# IRis_-_Slave_Schematic.net
KiCad netlist of a schematic drawn in EAGLE
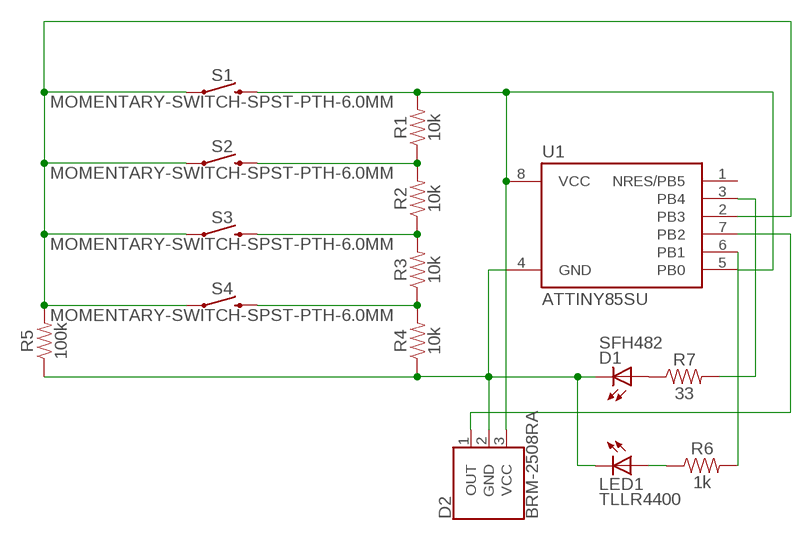
[diagram p0: schematic, sheet 1]

(export (version "E")
  (design (tool "Eeschema 10.0.6"))
  (components
    (comp (ref "D1")
      (value "SFH482")
      (footprint "eagle-import:SFH482")
      (libsource (lib "eagle-import") (part "SFH482"))
    )
    (comp (ref "D2")
      (value "BRM-2508RA")
      (footprint "eagle-import:BRM-2508")
      (libsource (lib "eagle-import") (part "BRM-2508RA"))
    )
    (comp (ref "LED1")
      (value "TLLR4400")
      (footprint "eagle-import:LED3MM")
      (fields (field (name "MF") "VISHAY SEMICONDUCTOR"))
      (libsource (lib "eagle-import") (part "TLLR4400"))
    )
    (comp (ref "R1")
      (value "10k")
      (footprint "eagle-import:AXIAL-0.3")
      (libsource (lib "eagle-import") (part "10KOHM-HORIZ-1/4W-5%"))
    )
    (comp (ref "R2")
      (value "10k")
      (footprint "eagle-import:AXIAL-0.3")
      (libsource (lib "eagle-import") (part "10KOHM-HORIZ-1/4W-5%"))
    )
    (comp (ref "R3")
      (value "10k")
      (footprint "eagle-import:AXIAL-0.3")
      (libsource (lib "eagle-import") (part "10KOHM-HORIZ-1/4W-5%"))
    )
    (comp (ref "R4")
      (value "10k")
      (footprint "eagle-import:AXIAL-0.3")
      (libsource (lib "eagle-import") (part "10KOHM-HORIZ-1/4W-5%"))
    )
    (comp (ref "R5")
      (value "100k")
      (footprint "eagle-import:AXIAL-0.3")
      (libsource (lib "eagle-import") (part "100KOHM-HORIZ-1/4W-5%"))
    )
    (comp (ref "R6")
      (value "1k")
      (footprint "eagle-import:AXIAL-0.3")
      (libsource (lib "eagle-import") (part "1KOHM-HORIZ-1/4W-5%"))
    )
    (comp (ref "R7")
      (value "33")
      (footprint "eagle-import:0603")
      (libsource (lib "eagle-import") (part "33OHM-0603-1/10W-1%"))
    )
    (comp (ref "S1")
      (value "MOMENTARY-SWITCH-SPST-PTH-6.0MM")
      (footprint "eagle-import:TACTILE_SWITCH_PTH_6.0MM")
      (libsource (lib "eagle-import") (part "MOMENTARY-SWITCH-SPST-PTH-6.0MM"))
    )
    (comp (ref "S2")
      (value "MOMENTARY-SWITCH-SPST-PTH-6.0MM")
      (footprint "eagle-import:TACTILE_SWITCH_PTH_6.0MM")
      (libsource (lib "eagle-import") (part "MOMENTARY-SWITCH-SPST-PTH-6.0MM"))
    )
    (comp (ref "S3")
      (value "MOMENTARY-SWITCH-SPST-PTH-6.0MM")
      (footprint "eagle-import:TACTILE_SWITCH_PTH_6.0MM")
      (libsource (lib "eagle-import") (part "MOMENTARY-SWITCH-SPST-PTH-6.0MM"))
    )
    (comp (ref "S4")
      (value "MOMENTARY-SWITCH-SPST-PTH-6.0MM")
      (footprint "eagle-import:TACTILE_SWITCH_PTH_6.0MM")
      (libsource (lib "eagle-import") (part "MOMENTARY-SWITCH-SPST-PTH-6.0MM"))
    )
    (comp (ref "U1")
      (value "ATTINY85SU")
      (footprint "eagle-import:ATTINY85")
      (libsource (lib "eagle-import") (part "ATTINY85SU"))
    )
  )
  (nets
    (net (code "1") (name "Net-(D1-C)") (class "Default")
      (node (ref "D1") (pin "K") (pinfunction "C_K") (pintype "passive"))
      (node (ref "D2") (pin "2") (pinfunction "GND_2") (pintype "bidirectional"))
      (node (ref "LED1") (pin "K") (pinfunction "C_K") (pintype "passive"))
      (node (ref "R4") (pin "P$1") (pinfunction "1_P$1") (pintype "passive"))
      (node (ref "R5") (pin "P$1") (pinfunction "1_P$1") (pintype "passive"))
      (node (ref "U1") (pin "4") (pinfunction "GND_4") (pintype "power_in"))
    )
    (net (code "2") (name "Net-(D1-PadA)") (class "Default")
      (node (ref "D1") (pin "A") (pinfunction "A_A") (pintype "passive"))
      (node (ref "R7") (pin "1") (pinfunction "1_1") (pintype "passive"))
    )
    (net (code "3") (name "Net-(D2-OUT)") (class "Default")
      (node (ref "D2") (pin "1") (pinfunction "OUT_1") (pintype "bidirectional"))
      (node (ref "U1") (pin "7") (pinfunction "PB2_7") (pintype "bidirectional"))
    )
    (net (code "4") (name "Net-(D2-VCC)") (class "Default")
      (node (ref "D2") (pin "3") (pinfunction "VCC_3") (pintype "bidirectional"))
      (node (ref "R1") (pin "P$2") (pinfunction "2_P$2") (pintype "passive"))
      (node (ref "S1") (pin "3") (pinfunction "2_3") (pintype "passive"))
      (node (ref "U1") (pin "5") (pinfunction "PB0_5") (pintype "bidirectional"))
      (node (ref "U1") (pin "8") (pinfunction "VCC_8") (pintype "power_in"))
    )
    (net (code "5") (name "Net-(R1-1)") (class "Default")
      (node (ref "R1") (pin "P$1") (pinfunction "1_P$1") (pintype "passive"))
      (node (ref "R2") (pin "P$2") (pinfunction "2_P$2") (pintype "passive"))
      (node (ref "S2") (pin "3") (pinfunction "2_3") (pintype "passive"))
    )
    (net (code "6") (name "Net-(R2-1)") (class "Default")
      (node (ref "R2") (pin "P$1") (pinfunction "1_P$1") (pintype "passive"))
      (node (ref "R3") (pin "P$2") (pinfunction "2_P$2") (pintype "passive"))
      (node (ref "S3") (pin "3") (pinfunction "2_3") (pintype "passive"))
    )
    (net (code "7") (name "Net-(R3-1)") (class "Default")
      (node (ref "R3") (pin "P$1") (pinfunction "1_P$1") (pintype "passive"))
      (node (ref "R4") (pin "P$2") (pinfunction "2_P$2") (pintype "passive"))
      (node (ref "S4") (pin "3") (pinfunction "2_3") (pintype "passive"))
    )
    (net (code "8") (name "Net-(R5-2)") (class "Default")
      (node (ref "R5") (pin "P$2") (pinfunction "2_P$2") (pintype "passive"))
      (node (ref "S1") (pin "1") (pinfunction "1_1") (pintype "passive"))
      (node (ref "S2") (pin "1") (pinfunction "1_1") (pintype "passive"))
      (node (ref "S3") (pin "1") (pinfunction "1_1") (pintype "passive"))
      (node (ref "S4") (pin "1") (pinfunction "1_1") (pintype "passive"))
      (node (ref "U1") (pin "2") (pinfunction "PB3_2") (pintype "bidirectional"))
    )
    (net (code "9") (name "Net-(R6-1)") (class "Default")
      (node (ref "LED1") (pin "A") (pinfunction "A_A") (pintype "passive"))
      (node (ref "R6") (pin "P$1") (pinfunction "1_P$1") (pintype "passive"))
    )
    (net (code "10") (name "Net-(R6-2)") (class "Default")
      (node (ref "R6") (pin "P$2") (pinfunction "2_P$2") (pintype "passive"))
      (node (ref "U1") (pin "6") (pinfunction "PB1_6") (pintype "bidirectional"))
    )
    (net (code "11") (name "Net-(U1-PB4)") (class "Default")
      (node (ref "R7") (pin "2") (pinfunction "2_2") (pintype "passive"))
      (node (ref "U1") (pin "3") (pinfunction "PB4_3") (pintype "bidirectional"))
    )
    (net (code "12") (name "unconnected-(U1-NRES{slash}PB5-Pad1)") (class "Default")
      (node (ref "U1") (pin "1") (pinfunction "NRES/PB5_1") (pintype "bidirectional"))
    )
  )
)
